# schematics.net
KiCad netlist of a schematic drawn in EAGLE
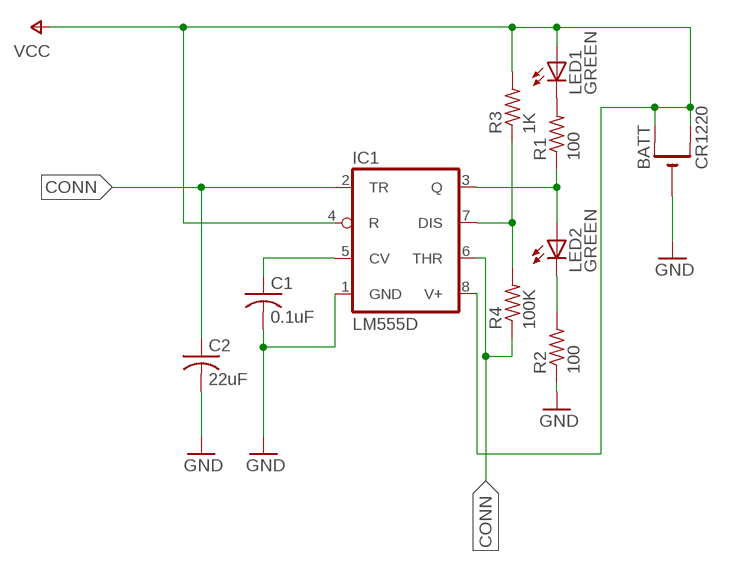
[diagram p0: schematic, sheet 1]

(export (version "E")
  (design (tool "Eeschema 10.0.6"))
  (components
    (comp (ref "BATT")
      (value "CR1220")
      (footprint "eagle-import:CR1220-SMD")
      (libsource (lib "eagle-import") (part "CR1220SMT"))
    )
    (comp (ref "C1")
      (value "0.1uF")
      (footprint "eagle-import:C0805")
      (libsource (lib "eagle-import") (part "C-USC0805"))
    )
    (comp (ref "C2")
      (value "22uF")
      (footprint "eagle-import:C0805")
      (libsource (lib "eagle-import") (part "C-USC0805"))
    )
    (comp (ref "IC1")
      (value "LM555D")
      (footprint "eagle-import:SO08")
      (libsource (lib "eagle-import") (part "555DLM"))
    )
    (comp (ref "LED1")
      (value "GREEN")
      (footprint "eagle-import:CHIPLED_0805")
      (libsource (lib "eagle-import") (part "LEDCHIPLED_0805"))
    )
    (comp (ref "LED2")
      (value "GREEN")
      (footprint "eagle-import:CHIPLED_0805")
      (libsource (lib "eagle-import") (part "LEDCHIPLED_0805"))
    )
    (comp (ref "R1")
      (value "100")
      (footprint "eagle-import:R0805")
      (libsource (lib "eagle-import") (part "R-US_R0805"))
    )
    (comp (ref "R2")
      (value "100")
      (footprint "eagle-import:R0805")
      (libsource (lib "eagle-import") (part "R-US_R0805"))
    )
    (comp (ref "R3")
      (value "1K")
      (footprint "eagle-import:R0805")
      (libsource (lib "eagle-import") (part "R-US_R0805"))
    )
    (comp (ref "R4")
      (value "100K")
      (footprint "eagle-import:R0805")
      (libsource (lib "eagle-import") (part "R-US_R0805"))
    )
  )
  (nets
    (net (code "1") (name "CONN") (class "Default")
      (node (ref "C2") (pin "1") (pinfunction "1_1") (pintype "passive"))
      (node (ref "IC1") (pin "2") (pinfunction "TR_2") (pintype "input"))
      (node (ref "IC1") (pin "6") (pinfunction "THR_6") (pintype "input"))
      (node (ref "R4") (pin "1") (pinfunction "1_1") (pintype "passive"))
    )
    (net (code "2") (name "GND") (class "Default")
      (node (ref "BATT") (pin "-") (pinfunction "-_-") (pintype "passive"))
      (node (ref "C1") (pin "2") (pinfunction "2_2") (pintype "passive"))
      (node (ref "C2") (pin "2") (pinfunction "2_2") (pintype "passive"))
      (node (ref "IC1") (pin "1") (pinfunction "GND_1") (pintype "power_in"))
      (node (ref "R2") (pin "1") (pinfunction "1_1") (pintype "passive"))
    )
    (net (code "3") (name "Net-(IC1-CV)") (class "Default")
      (node (ref "C1") (pin "1") (pinfunction "1_1") (pintype "passive"))
      (node (ref "IC1") (pin "5") (pinfunction "CV_5") (pintype "input"))
    )
    (net (code "4") (name "Net-(IC1-DIS)") (class "Default")
      (node (ref "IC1") (pin "7") (pinfunction "DIS_7") (pintype "input"))
      (node (ref "R3") (pin "1") (pinfunction "1_1") (pintype "passive"))
      (node (ref "R4") (pin "2") (pinfunction "2_2") (pintype "passive"))
    )
    (net (code "5") (name "Net-(IC1-Q)") (class "Default")
      (node (ref "IC1") (pin "3") (pinfunction "Q_3") (pintype "output"))
      (node (ref "LED2") (pin "A") (pinfunction "A_A") (pintype "passive"))
      (node (ref "R1") (pin "1") (pinfunction "1_1") (pintype "passive"))
    )
    (net (code "6") (name "Net-(LED1-PadC)") (class "Default")
      (node (ref "LED1") (pin "C") (pinfunction "C_C") (pintype "passive"))
      (node (ref "R1") (pin "2") (pinfunction "2_2") (pintype "passive"))
    )
    (net (code "7") (name "Net-(LED2-PadC)") (class "Default")
      (node (ref "LED2") (pin "C") (pinfunction "C_C") (pintype "passive"))
      (node (ref "R2") (pin "2") (pinfunction "2_2") (pintype "passive"))
    )
    (net (code "8") (name "VCC") (class "Default")
      (node (ref "BATT") (pin "+$1") (pinfunction "+_+$1") (pintype "passive"))
      (node (ref "BATT") (pin "+$2") (pinfunction "+1_+$2") (pintype "passive"))
      (node (ref "IC1") (pin "4") (pinfunction "R_4") (pintype "input"))
      (node (ref "IC1") (pin "8") (pinfunction "V+_8") (pintype "power_in"))
      (node (ref "LED1") (pin "A") (pinfunction "A_A") (pintype "passive"))
      (node (ref "R3") (pin "2") (pinfunction "2_2") (pintype "passive"))
    )
  )
)
